# Power_Connections.net
KiCad netlist of a schematic drawn in Altium Designer
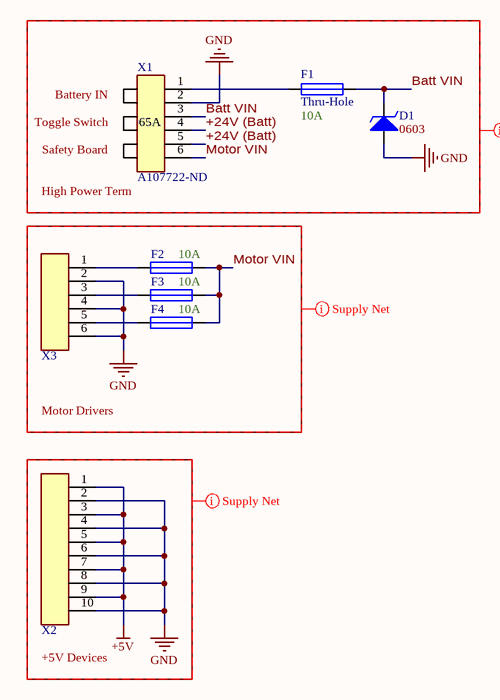
[diagram p0: Power Connections.SchDoc]

(export (version "E")
  (design (tool "Eeschema 10.0.6"))
  (components
    (comp (ref "D1")
      (value "TVS/Zener")
      (footprint "[Diode] SMD 0603")
      (description "Generic")
      (fields (field (name "SIZE PACKAGE") "0603"))
      (libsource (lib "RADM Components") (part "[Diode] TVS Diode"))
    )
    (comp (ref "F1")
      (value "Thru-Hole")
      (footprint "[Fuse] Blade (2)")
      (fields (field (name "CAPACITY") "10A"))
      (libsource (lib "RADM Components") (part "[Fuse] Thru-Hole Blade"))
    )
    (comp (ref "F2")
      (value "Thru-Hole")
      (footprint "[Fuse] Blade (2)")
      (fields (field (name "CAPACITY") "10A"))
      (libsource (lib "RADM Components") (part "[Fuse] Thru-Hole Blade"))
    )
    (comp (ref "F3")
      (value "Thru-Hole")
      (footprint "[Fuse] Blade (2)")
      (fields (field (name "CAPACITY") "10A"))
      (libsource (lib "RADM Components") (part "[Fuse] Thru-Hole Blade"))
    )
    (comp (ref "F4")
      (value "Thru-Hole")
      (footprint "[Fuse] Blade (2)")
      (fields (field (name "CAPACITY") "10A"))
      (libsource (lib "RADM Components") (part "[Fuse] Thru-Hole Blade"))
    )
    (comp (ref "X1")
      (value "[Screw Terminal] 6pin 65A")
      (footprint "[Screw Terminal] 6pin 65A")
      (description "Remember to order 3 of the screw term for one of these!")
      (fields (field (name "SUPPLIER PART NUMBER 1") "A107722-ND"))
      (libsource (lib "RADM Connectors") (part "[Screw Terminal] 6pin 65A"))
    )
    (comp (ref "X2")
      (value "[Screw Terminal] 10pin")
      (footprint "[Screw Terminal] 10pin")
      (description "x5")
      (libsource (lib "RADM Connectors") (part "[Screw Terminal] 10pin"))
    )
    (comp (ref "X3")
      (value "[Screw Terminal] 6pin")
      (footprint "[Screw Terminal] 6pin")
      (description "x3")
      (libsource (lib "RADM Connectors") (part "[Screw Terminal] 6pin"))
    )
  )
  (nets
    (net (code "1") (name "+5V") (class "Default")
      (node (ref "X2") (pin "1") (pintype "power_in"))
      (node (ref "X2") (pin "3") (pintype "power_in"))
      (node (ref "X2") (pin "5") (pintype "power_in"))
      (node (ref "X2") (pin "7") (pintype "power_in"))
      (node (ref "X2") (pin "9") (pintype "power_in"))
    )
    (net (code "2") (name "/+24V (Batt)") (class "Default")
      (node (ref "X1") (pin "4") (pintype "passive"))
      (node (ref "X1") (pin "5") (pinfunction "5_5") (pintype "power_in"))
    )
    (net (code "3") (name "/Batt VIN") (class "Default")
      (node (ref "D1") (pin "1") (pinfunction "Cathode_1") (pintype "passive"))
      (node (ref "F1") (pin "2") (pinfunction "2_2") (pintype "passive"))
      (node (ref "X1") (pin "3") (pintype "passive"))
    )
    (net (code "4") (name "/Motor VIN") (class "Default")
      (node (ref "F2") (pin "2") (pinfunction "2_2") (pintype "passive"))
      (node (ref "F3") (pin "2") (pinfunction "2_2") (pintype "passive"))
      (node (ref "F4") (pin "2") (pinfunction "2_2") (pintype "passive"))
      (node (ref "X1") (pin "6") (pinfunction "6_6") (pintype "power_in"))
    )
    (net (code "5") (name "GND") (class "Default")
      (node (ref "D1") (pin "2") (pinfunction "Anode_2") (pintype "passive"))
      (node (ref "X1") (pin "2") (pintype "passive"))
      (node (ref "X2") (pin "10") (pintype "power_in"))
      (node (ref "X2") (pin "2") (pintype "power_in"))
      (node (ref "X2") (pin "4") (pintype "power_in"))
      (node (ref "X2") (pin "6") (pintype "power_in"))
      (node (ref "X2") (pin "8") (pintype "power_in"))
      (node (ref "X3") (pin "2") (pintype "power_in"))
      (node (ref "X3") (pin "4") (pintype "power_in"))
      (node (ref "X3") (pin "6") (pintype "power_in"))
    )
    (net (code "6") (name "Net-(F1-Pad1)") (class "Default")
      (node (ref "F1") (pin "1") (pinfunction "1_1") (pintype "passive"))
      (node (ref "X1") (pin "1") (pintype "passive"))
    )
    (net (code "7") (name "Net-(F2-Pad1)") (class "Default")
      (node (ref "F2") (pin "1") (pinfunction "1_1") (pintype "passive"))
      (node (ref "X3") (pin "1") (pintype "power_in"))
    )
    (net (code "8") (name "Net-(F3-Pad1)") (class "Default")
      (node (ref "F3") (pin "1") (pinfunction "1_1") (pintype "passive"))
      (node (ref "X3") (pin "3") (pintype "power_in"))
    )
    (net (code "9") (name "Net-(F4-Pad1)") (class "Default")
      (node (ref "F4") (pin "1") (pinfunction "1_1") (pintype "passive"))
      (node (ref "X3") (pin "5") (pintype "power_in"))
    )
  )
)
